# ReflowController_v1_2.net
KiCad netlist of a schematic drawn in EAGLE
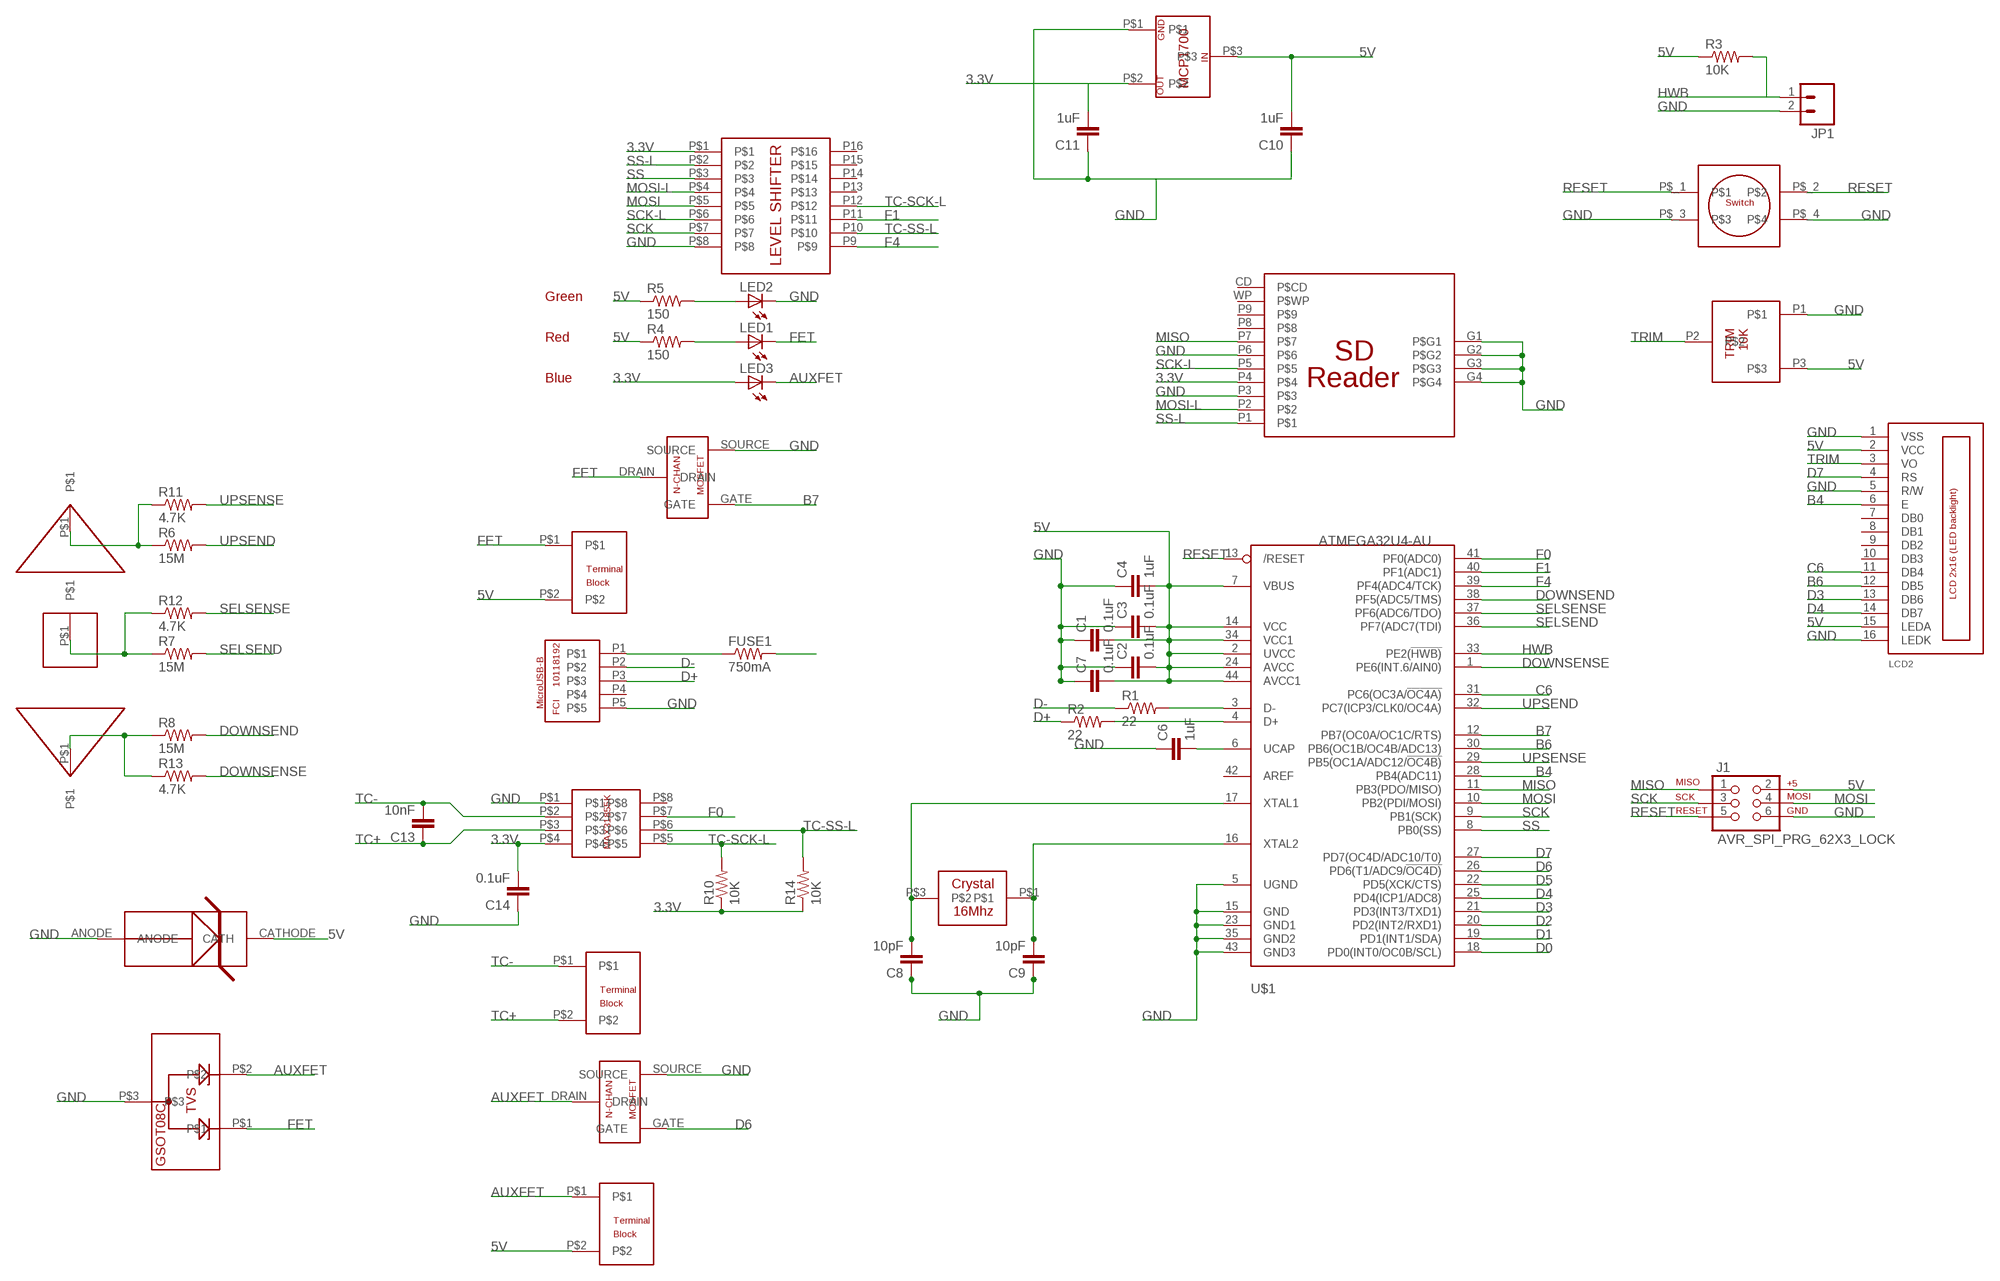
[diagram p0: schematic, sheet 1]

(export (version "E")
  (design (tool "Eeschema 10.0.6"))
  (components
    (comp (ref "C1")
      (value "0.1uF")
      (footprint "eagle-import:0603-CAP")
      (libsource (lib "eagle-import") (part "CAP0603-CAP"))
    )
    (comp (ref "C2")
      (value "0.1uF")
      (footprint "eagle-import:0603-CAP")
      (libsource (lib "eagle-import") (part "CAP0603-CAP"))
    )
    (comp (ref "C3")
      (value "0.1uF")
      (footprint "eagle-import:0603-CAP")
      (libsource (lib "eagle-import") (part "CAP0603-CAP"))
    )
    (comp (ref "C4")
      (value "1uF")
      (footprint "eagle-import:0603-CAP")
      (libsource (lib "eagle-import") (part "CAP0603-CAP"))
    )
    (comp (ref "C6")
      (value "1uF")
      (footprint "eagle-import:0603-CAP")
      (libsource (lib "eagle-import") (part "CAP0603-CAP"))
    )
    (comp (ref "C7")
      (value "0.1uF")
      (footprint "eagle-import:0603-CAP")
      (libsource (lib "eagle-import") (part "CAP0603-CAP"))
    )
    (comp (ref "C8")
      (value "10pF")
      (footprint "eagle-import:0603-CAP")
      (libsource (lib "eagle-import") (part "CAP0603-CAP"))
    )
    (comp (ref "C9")
      (value "10pF")
      (footprint "eagle-import:0603-CAP")
      (libsource (lib "eagle-import") (part "CAP0603-CAP"))
    )
    (comp (ref "C10")
      (value "1uF")
      (footprint "eagle-import:0603-CAP")
      (libsource (lib "eagle-import") (part "CAP0603-CAP"))
    )
    (comp (ref "C11")
      (value "1uF")
      (footprint "eagle-import:0603-CAP")
      (libsource (lib "eagle-import") (part "CAP0603-CAP"))
    )
    (comp (ref "C13")
      (value "10nF")
      (footprint "eagle-import:0603-CAP")
      (libsource (lib "eagle-import") (part "CAP0603-CAP"))
    )
    (comp (ref "C14")
      (value "0.1uF")
      (footprint "eagle-import:0603-CAP")
      (libsource (lib "eagle-import") (part "CAP0603-CAP"))
    )
    (comp (ref "FUSE1")
      (value "750mA")
      (footprint "eagle-import:0603-RES")
      (libsource (lib "eagle-import") (part "RESISTOR0603-RES"))
    )
    (comp (ref "J1")
      (value "AVR_SPI_PRG_62X3_LOCK")
      (footprint "eagle-import:2X3_LOCK")
      (libsource (lib "eagle-import") (part "AVR_SPI_PRG_62X3_LOCK"))
    )
    (comp (ref "JP1")
      (value "M02PTH")
      (footprint "eagle-import:1X02")
      (libsource (lib "eagle-import") (part "M02PTH"))
    )
    (comp (ref "LCD2")
      (value "LCD_2X16_SIL")
      (footprint "eagle-import:HY-1602F")
      (libsource (lib "eagle-import") (part "LCD_2X16_SIL"))
    )
    (comp (ref "LED1")
      (value "LED0603")
      (footprint "eagle-import:LED-0603")
      (libsource (lib "eagle-import") (part "LED0603"))
    )
    (comp (ref "LED2")
      (value "LED0603")
      (footprint "eagle-import:LED-0603")
      (libsource (lib "eagle-import") (part "LED0603"))
    )
    (comp (ref "LED3")
      (value "LED0603")
      (footprint "eagle-import:LED-0603")
      (libsource (lib "eagle-import") (part "LED0603"))
    )
    (comp (ref "R1")
      (value "22")
      (footprint "eagle-import:0603-RES")
      (libsource (lib "eagle-import") (part "RESISTOR0603-RES"))
    )
    (comp (ref "R2")
      (value "22")
      (footprint "eagle-import:0603-RES")
      (libsource (lib "eagle-import") (part "RESISTOR0603-RES"))
    )
    (comp (ref "R3")
      (value "10K")
      (footprint "eagle-import:0603-RES")
      (libsource (lib "eagle-import") (part "RESISTOR0603-RES"))
    )
    (comp (ref "R4")
      (value "150")
      (footprint "eagle-import:0603-RES")
      (libsource (lib "eagle-import") (part "RESISTOR0603-RES"))
    )
    (comp (ref "R5")
      (value "150")
      (footprint "eagle-import:0603-RES")
      (libsource (lib "eagle-import") (part "RESISTOR0603-RES"))
    )
    (comp (ref "R6")
      (value "15M")
      (footprint "eagle-import:0603-RES")
      (libsource (lib "eagle-import") (part "RESISTOR0603-RES"))
    )
    (comp (ref "R7")
      (value "15M")
      (footprint "eagle-import:0603-RES")
      (libsource (lib "eagle-import") (part "RESISTOR0603-RES"))
    )
    (comp (ref "R8")
      (value "15M")
      (footprint "eagle-import:0603-RES")
      (libsource (lib "eagle-import") (part "RESISTOR0603-RES"))
    )
    (comp (ref "R10")
      (value "10K")
      (footprint "eagle-import:0603-RES")
      (libsource (lib "eagle-import") (part "RESISTOR0603-RES"))
    )
    (comp (ref "R11")
      (value "4.7K")
      (footprint "eagle-import:0603-RES")
      (libsource (lib "eagle-import") (part "RESISTOR0603-RES"))
    )
    (comp (ref "R12")
      (value "4.7K")
      (footprint "eagle-import:0603-RES")
      (libsource (lib "eagle-import") (part "RESISTOR0603-RES"))
    )
    (comp (ref "R13")
      (value "4.7K")
      (footprint "eagle-import:0603-RES")
      (libsource (lib "eagle-import") (part "RESISTOR0603-RES"))
    )
    (comp (ref "R14")
      (value "10K")
      (footprint "eagle-import:0603-RES")
      (libsource (lib "eagle-import") (part "RESISTOR0603-RES"))
    )
    (comp (ref "U$1")
      (value "ATMEGA32U4-AU")
      (footprint "eagle-import:TQFP44")
      (libsource (lib "eagle-import") (part "ATMEGA32U4-AU"))
    )
    (comp (ref "U$2")
      (value "16MHZ-CRYSTAL_NX3225GA-16.000M-STD-CRG-1")
      (footprint "eagle-import:16MHZ-CRYSTAL_NX3225GA-16.000M-STD-CRG-1")
      (libsource (lib "eagle-import") (part "16MHZ-CRYSTAL_NX3225GA-16.000M-STD-CRG-1"))
    )
    (comp (ref "U$3")
      (value "USB-B_10118192-0001LF")
      (footprint "eagle-import:USB-B_10118192-0001LF")
      (libsource (lib "eagle-import") (part "USB-B_10118192-0001LF"))
    )
    (comp (ref "U$4")
      (value "SDREADER_2041021-4")
      (footprint "eagle-import:SDREADER_2041021-4")
      (libsource (lib "eagle-import") (part "SDREADER_2041021-4"))
    )
    (comp (ref "U$5")
      (value "2POS_TERM_ED2748-ND")
      (footprint "eagle-import:2POS_TERM_ED2748-ND")
      (libsource (lib "eagle-import") (part "2POS_TERM_ED2748-ND"))
    )
    (comp (ref "U$6")
      (value "N-MOSFET630_DMG1012T-7DICT-ND")
      (footprint "eagle-import:N-MOSFET630_DMG1012T-7DICT-ND")
      (libsource (lib "eagle-import") (part "N-MOSFET630_DMG1012T-7DICT-ND"))
    )
    (comp (ref "U$7")
      (value "2POS_TERM_ED2748-ND")
      (footprint "eagle-import:2POS_TERM_ED2748-ND")
      (libsource (lib "eagle-import") (part "2POS_TERM_ED2748-ND"))
    )
    (comp (ref "U$8")
      (value "NXP_LVL_SHIFT_74HC4050D,653")
      (footprint "eagle-import:NXP_LVL_SHIFT_74HC4050D,653")
      (libsource (lib "eagle-import") (part "NXP_LVL_SHIFT_74HC4050D,653"))
    )
    (comp (ref "U$9")
      (value "MAX_TC_MAX31855KASA+")
      (footprint "eagle-import:MAX_TC_MAX31855KASA+")
      (libsource (lib "eagle-import") (part "MAX_TC_MAX31855KASA+"))
    )
    (comp (ref "U$10")
      (value "10K_TRIM_3362F-1-103LF")
      (footprint "eagle-import:10K_TRIM_3362F-1-103LF")
      (libsource (lib "eagle-import") (part "10K_TRIM_3362F-1-103LF"))
    )
    (comp (ref "U$11")
      (value "MCP1700__LDO")
      (footprint "eagle-import:MCP1700__LDO")
      (libsource (lib "eagle-import") (part "MCP1700__LDO"))
    )
    (comp (ref "U$12")
      (value "MOM-SWITCH-EG4620CT-ND")
      (footprint "eagle-import:MOM-SWITCH-EG4620CT-ND")
      (libsource (lib "eagle-import") (part "MOM-SWITCH-EG4620CT-ND"))
    )
    (comp (ref "U$13")
      (value "CAPTOUCH_ARROW")
      (footprint "eagle-import:CAPTOUCH_ARROW")
      (libsource (lib "eagle-import") (part "CAPTOUCH_ARROW"))
    )
    (comp (ref "U$14")
      (value "CAPTOUCH_ARROW")
      (footprint "eagle-import:CAPTOUCH_ARROW")
      (libsource (lib "eagle-import") (part "CAPTOUCH_ARROW"))
    )
    (comp (ref "U$15")
      (value "CAPTOUCH_SQUARE")
      (footprint "eagle-import:CAPTOUCH_SQUARE")
      (libsource (lib "eagle-import") (part "CAPTOUCH_SQUARE"))
    )
    (comp (ref "U$16")
      (value "N-MOSFET630_DMG1012T-7DICT-ND")
      (footprint "eagle-import:N-MOSFET630_DMG1012T-7DICT-ND")
      (libsource (lib "eagle-import") (part "N-MOSFET630_DMG1012T-7DICT-ND"))
    )
    (comp (ref "U$17")
      (value "2POS_TERM_ED2748-ND")
      (footprint "eagle-import:2POS_TERM_ED2748-ND")
      (libsource (lib "eagle-import") (part "2POS_TERM_ED2748-ND"))
    )
    (comp (ref "U$18")
      (value "TVS_DIODE_MATRIX_GSOT08C-GS08")
      (footprint "eagle-import:TVS_DIODE_MATRIX_GSOT08C-GS08")
      (libsource (lib "eagle-import") (part "TVS_DIODE_MATRIX_GSOT08C-GS08"))
    )
    (comp (ref "U$19")
      (value "TVS_DIODE_1CH_1SMB6.0AT3G")
      (footprint "eagle-import:TVS_DIODE_1CH_1SMB6.0AT3G")
      (libsource (lib "eagle-import") (part "TVS_DIODE_1CH_1SMB6.0AT3G"))
    )
  )
  (nets
    (net (code "1") (name "/3.3V") (class "Default")
      (node (ref "C11") (pin "2") (pinfunction "2_2") (pintype "passive"))
      (node (ref "C14") (pin "2") (pinfunction "2_2") (pintype "passive"))
      (node (ref "LED3") (pin "A") (pinfunction "A_A") (pintype "passive"))
      (node (ref "R10") (pin "1") (pinfunction "1_1") (pintype "passive"))
      (node (ref "R14") (pin "1") (pinfunction "1_1") (pintype "passive"))
      (node (ref "U$11") (pin "P$2") (pinfunction "P$2_P$2") (pintype "bidirectional"))
      (node (ref "U$4") (pin "P4") (pinfunction "P$4_P4") (pintype "bidirectional"))
      (node (ref "U$8") (pin "P$1") (pinfunction "P$1_P$1") (pintype "bidirectional"))
      (node (ref "U$9") (pin "P$4") (pinfunction "P$4_P$4") (pintype "bidirectional"))
    )
    (net (code "2") (name "/5V") (class "Default")
      (node (ref "C1") (pin "2") (pinfunction "2_2") (pintype "passive"))
      (node (ref "C10") (pin "2") (pinfunction "2_2") (pintype "passive"))
      (node (ref "C2") (pin "2") (pinfunction "2_2") (pintype "passive"))
      (node (ref "C3") (pin "2") (pinfunction "2_2") (pintype "passive"))
      (node (ref "C4") (pin "2") (pinfunction "2_2") (pintype "passive"))
      (node (ref "C7") (pin "2") (pinfunction "2_2") (pintype "passive"))
      (node (ref "FUSE1") (pin "2") (pinfunction "2_2") (pintype "passive"))
      (node (ref "J1") (pin "2") (pinfunction "2_2") (pintype "passive"))
      (node (ref "LCD2") (pin "15") (pinfunction "LEDA_15") (pintype "passive"))
      (node (ref "LCD2") (pin "2") (pinfunction "VCC_2") (pintype "power_in"))
      (node (ref "R3") (pin "1") (pinfunction "1_1") (pintype "passive"))
      (node (ref "R4") (pin "1") (pinfunction "1_1") (pintype "passive"))
      (node (ref "R5") (pin "1") (pinfunction "1_1") (pintype "passive"))
      (node (ref "U$1") (pin "14") (pinfunction "VCC_14") (pintype "bidirectional"))
      (node (ref "U$1") (pin "2") (pinfunction "UVCC_2") (pintype "bidirectional"))
      (node (ref "U$1") (pin "24") (pinfunction "AVCC_24") (pintype "bidirectional"))
      (node (ref "U$1") (pin "34") (pinfunction "VCC1_34") (pintype "bidirectional"))
      (node (ref "U$1") (pin "44") (pinfunction "AVCC1_44") (pintype "bidirectional"))
      (node (ref "U$1") (pin "7") (pinfunction "VBUS_7") (pintype "bidirectional"))
      (node (ref "U$10") (pin "P3") (pinfunction "P$3_P3") (pintype "bidirectional"))
      (node (ref "U$11") (pin "P$3") (pinfunction "P$3_P$3") (pintype "bidirectional"))
      (node (ref "U$17") (pin "P$2") (pinfunction "P$2_P$2") (pintype "bidirectional"))
      (node (ref "U$19") (pin "CATHODE") (pinfunction "CATH_CATHODE") (pintype "bidirectional"))
      (node (ref "U$5") (pin "P$2") (pinfunction "P$2_P$2") (pintype "bidirectional"))
    )
    (net (code "3") (name "/AUXFET") (class "Default")
      (node (ref "LED3") (pin "C") (pinfunction "C_C") (pintype "passive"))
      (node (ref "U$16") (pin "DRAIN") (pinfunction "DRAIN_DRAIN") (pintype "bidirectional"))
      (node (ref "U$17") (pin "P$1") (pinfunction "P$1_P$1") (pintype "bidirectional"))
      (node (ref "U$18") (pin "P$2") (pinfunction "P$2_P$2") (pintype "bidirectional"))
    )
    (net (code "4") (name "/B4") (class "Default")
      (node (ref "LCD2") (pin "6") (pinfunction "E_6") (pintype "input"))
      (node (ref "U$1") (pin "28") (pinfunction "PB4(ADC11)_28") (pintype "bidirectional"))
    )
    (net (code "5") (name "/B6") (class "Default")
      (node (ref "LCD2") (pin "12") (pinfunction "DB5_12") (pintype "bidirectional"))
      (node (ref "U$1") (pin "30") (pinfunction "PB6(OC1B/OC4B/ADC13)_30") (pintype "bidirectional"))
    )
    (net (code "6") (name "/B7") (class "Default")
      (node (ref "U$1") (pin "12") (pinfunction "PB7(OC0A/OC1C/RTS)_12") (pintype "bidirectional"))
      (node (ref "U$6") (pin "GATE") (pinfunction "GATE_GATE") (pintype "bidirectional"))
    )
    (net (code "7") (name "/C6") (class "Default")
      (node (ref "LCD2") (pin "11") (pinfunction "DB4_11") (pintype "bidirectional"))
      (node (ref "U$1") (pin "31") (pinfunction "PC6(OC3A/~{OC4A})_31") (pintype "bidirectional"))
    )
    (net (code "8") (name "/D+") (class "Default")
      (node (ref "R2") (pin "1") (pinfunction "1_1") (pintype "passive"))
      (node (ref "U$3") (pin "P3") (pinfunction "P$3_P3") (pintype "bidirectional"))
    )
    (net (code "9") (name "/D-") (class "Default")
      (node (ref "R1") (pin "1") (pinfunction "1_1") (pintype "passive"))
      (node (ref "U$3") (pin "P2") (pinfunction "P$2_P2") (pintype "bidirectional"))
    )
    (net (code "10") (name "/D0") (class "Default")
      (node (ref "U$1") (pin "18") (pinfunction "PD0(INT0/OC0B/SCL)_18") (pintype "bidirectional"))
    )
    (net (code "11") (name "/D1") (class "Default")
      (node (ref "U$1") (pin "19") (pinfunction "PD1(INT1/SDA)_19") (pintype "bidirectional"))
    )
    (net (code "12") (name "/D2") (class "Default")
      (node (ref "U$1") (pin "20") (pinfunction "PD2(INT2/RXD1)_20") (pintype "bidirectional"))
    )
    (net (code "13") (name "/D3") (class "Default")
      (node (ref "LCD2") (pin "13") (pinfunction "DB6_13") (pintype "bidirectional"))
      (node (ref "U$1") (pin "21") (pinfunction "PD3(INT3/TXD1)_21") (pintype "bidirectional"))
    )
    (net (code "14") (name "/D4") (class "Default")
      (node (ref "LCD2") (pin "14") (pinfunction "DB7_14") (pintype "bidirectional"))
      (node (ref "U$1") (pin "25") (pinfunction "PD4(ICP1/ADC8)_25") (pintype "bidirectional"))
    )
    (net (code "15") (name "/D5") (class "Default")
      (node (ref "U$1") (pin "22") (pinfunction "PD5(XCK/CTS)_22") (pintype "bidirectional"))
    )
    (net (code "16") (name "/D6") (class "Default")
      (node (ref "U$1") (pin "26") (pinfunction "PD6(T1/ADC9/~{OC4D})_26") (pintype "bidirectional"))
      (node (ref "U$16") (pin "GATE") (pinfunction "GATE_GATE") (pintype "bidirectional"))
    )
    (net (code "17") (name "/D7") (class "Default")
      (node (ref "LCD2") (pin "4") (pinfunction "RS_4") (pintype "input"))
      (node (ref "U$1") (pin "27") (pinfunction "PD7(OC4D/ADC10/T0)_27") (pintype "bidirectional"))
    )
    (net (code "18") (name "/DOWNSEND") (class "Default")
      (node (ref "R8") (pin "2") (pinfunction "2_2") (pintype "passive"))
      (node (ref "U$1") (pin "38") (pinfunction "PF5(ADC5/TMS)_38") (pintype "bidirectional"))
    )
    (net (code "19") (name "/DOWNSENSE") (class "Default")
      (node (ref "R13") (pin "2") (pinfunction "2_2") (pintype "passive"))
      (node (ref "U$1") (pin "1") (pinfunction "PE6(INT.6/AIN0)_1") (pintype "bidirectional"))
    )
    (net (code "20") (name "/F0") (class "Default")
      (node (ref "U$1") (pin "41") (pinfunction "PF0(ADC0)_41") (pintype "bidirectional"))
      (node (ref "U$9") (pin "P$7") (pinfunction "P$7_P$7") (pintype "bidirectional"))
    )
    (net (code "21") (name "/F1") (class "Default")
      (node (ref "U$1") (pin "40") (pinfunction "PF1(ADC1)_40") (pintype "bidirectional"))
      (node (ref "U$8") (pin "P11") (pinfunction "P$11_P11") (pintype "bidirectional"))
    )
    (net (code "22") (name "/F4") (class "Default")
      (node (ref "U$1") (pin "39") (pinfunction "PF4(ADC4/TCK)_39") (pintype "bidirectional"))
      (node (ref "U$8") (pin "P9") (pinfunction "P$9_P9") (pintype "bidirectional"))
    )
    (net (code "23") (name "/FET") (class "Default")
      (node (ref "LED1") (pin "C") (pinfunction "C_C") (pintype "passive"))
      (node (ref "U$18") (pin "P$1") (pinfunction "P$1_P$1") (pintype "bidirectional"))
      (node (ref "U$5") (pin "P$1") (pinfunction "P$1_P$1") (pintype "bidirectional"))
      (node (ref "U$6") (pin "DRAIN") (pinfunction "DRAIN_DRAIN") (pintype "bidirectional"))
    )
    (net (code "24") (name "/GND") (class "Default")
      (node (ref "C1") (pin "1") (pinfunction "1_1") (pintype "passive"))
      (node (ref "C10") (pin "1") (pinfunction "1_1") (pintype "passive"))
      (node (ref "C11") (pin "1") (pinfunction "1_1") (pintype "passive"))
      (node (ref "C14") (pin "1") (pinfunction "1_1") (pintype "passive"))
      (node (ref "C2") (pin "1") (pinfunction "1_1") (pintype "passive"))
      (node (ref "C3") (pin "1") (pinfunction "1_1") (pintype "passive"))
      (node (ref "C4") (pin "1") (pinfunction "1_1") (pintype "passive"))
      (node (ref "C6") (pin "1") (pinfunction "1_1") (pintype "passive"))
      (node (ref "C7") (pin "1") (pinfunction "1_1") (pintype "passive"))
      (node (ref "C8") (pin "1") (pinfunction "1_1") (pintype "passive"))
      (node (ref "C9") (pin "1") (pinfunction "1_1") (pintype "passive"))
      (node (ref "J1") (pin "6") (pinfunction "6_6") (pintype "passive"))
      (node (ref "JP1") (pin "2") (pinfunction "2_2") (pintype "passive"))
      (node (ref "LCD2") (pin "1") (pinfunction "VSS_1") (pintype "power_in"))
      (node (ref "LCD2") (pin "16") (pinfunction "LEDK_16") (pintype "passive"))
      (node (ref "LCD2") (pin "5") (pinfunction "R/W_5") (pintype "input"))
      (node (ref "LED2") (pin "C") (pinfunction "C_C") (pintype "passive"))
      (node (ref "U$1") (pin "15") (pinfunction "GND_15") (pintype "bidirectional"))
      (node (ref "U$1") (pin "23") (pinfunction "GND1_23") (pintype "bidirectional"))
      (node (ref "U$1") (pin "35") (pinfunction "GND2_35") (pintype "bidirectional"))
      (node (ref "U$1") (pin "43") (pinfunction "GND3_43") (pintype "bidirectional"))
      (node (ref "U$1") (pin "5") (pinfunction "UGND_5") (pintype "bidirectional"))
      (node (ref "U$10") (pin "P1") (pinfunction "P$1_P1") (pintype "bidirectional"))
      (node (ref "U$11") (pin "P$1") (pinfunction "P$1_P$1") (pintype "bidirectional"))
      (node (ref "U$12") (pin "P$_3") (pinfunction "P$3_P$_3") (pintype "bidirectional"))
      (node (ref "U$12") (pin "P$_4") (pinfunction "P$4_P$_4") (pintype "bidirectional"))
      (node (ref "U$16") (pin "SOURCE") (pinfunction "SOURCE_SOURCE") (pintype "bidirectional"))
      (node (ref "U$18") (pin "P$3") (pinfunction "P$3_P$3") (pintype "bidirectional"))
      (node (ref "U$19") (pin "ANODE") (pinfunction "ANODE_ANODE") (pintype "bidirectional"))
      (node (ref "U$3") (pin "P5") (pinfunction "P$5_P5") (pintype "bidirectional"))
      (node (ref "U$4") (pin "G1") (pinfunction "P$G1_G1") (pintype "bidirectional"))
      (node (ref "U$4") (pin "G2") (pinfunction "P$G2_G2") (pintype "bidirectional"))
      (node (ref "U$4") (pin "G3") (pinfunction "P$G3_G3") (pintype "bidirectional"))
      (node (ref "U$4") (pin "G4") (pinfunction "P$G4_G4") (pintype "bidirectional"))
      (node (ref "U$4") (pin "P3") (pinfunction "P$3_P3") (pintype "bidirectional"))
      (node (ref "U$4") (pin "P6") (pinfunction "P$6_P6") (pintype "bidirectional"))
      (node (ref "U$6") (pin "SOURCE") (pinfunction "SOURCE_SOURCE") (pintype "bidirectional"))
      (node (ref "U$8") (pin "P$8") (pinfunction "P$8_P$8") (pintype "bidirectional"))
      (node (ref "U$9") (pin "P$1") (pinfunction "P$1_P$1") (pintype "bidirectional"))
    )
    (net (code "25") (name "/HWB") (class "Default")
      (node (ref "JP1") (pin "1") (pinfunction "1_1") (pintype "passive"))
      (node (ref "R3") (pin "2") (pinfunction "2_2") (pintype "passive"))
      (node (ref "U$1") (pin "33") (pinfunction "PE2(~{HWB})_33") (pintype "bidirectional"))
    )
    (net (code "26") (name "/MISO") (class "Default")
      (node (ref "J1") (pin "1") (pinfunction "1_1") (pintype "passive"))
      (node (ref "U$1") (pin "11") (pinfunction "PB3(PDO/MISO)_11") (pintype "bidirectional"))
      (node (ref "U$4") (pin "P7") (pinfunction "P$7_P7") (pintype "bidirectional"))
    )
    (net (code "27") (name "/MOSI") (class "Default")
      (node (ref "J1") (pin "4") (pinfunction "4_4") (pintype "passive"))
      (node (ref "U$1") (pin "10") (pinfunction "PB2(PDI/MOSI)_10") (pintype "bidirectional"))
      (node (ref "U$8") (pin "P$5") (pinfunction "P$5_P$5") (pintype "bidirectional"))
    )
    (net (code "28") (name "/MOSI-L") (class "Default")
      (node (ref "U$4") (pin "P2") (pinfunction "P$2_P2") (pintype "bidirectional"))
      (node (ref "U$8") (pin "P$4") (pinfunction "P$4_P$4") (pintype "bidirectional"))
    )
    (net (code "29") (name "/RESET") (class "Default")
      (node (ref "J1") (pin "5") (pinfunction "5_5") (pintype "passive"))
      (node (ref "U$1") (pin "13") (pinfunction "/RESET_13") (pintype "bidirectional"))
      (node (ref "U$12") (pin "P$_1") (pinfunction "P$1_P$_1") (pintype "bidirectional"))
      (node (ref "U$12") (pin "P$_2") (pinfunction "P$2_P$_2") (pintype "bidirectional"))
    )
    (net (code "30") (name "/SCK") (class "Default")
      (node (ref "J1") (pin "3") (pinfunction "3_3") (pintype "passive"))
      (node (ref "U$1") (pin "9") (pinfunction "PB1(SCK)_9") (pintype "bidirectional"))
      (node (ref "U$8") (pin "P$7") (pinfunction "P$7_P$7") (pintype "bidirectional"))
    )
    (net (code "31") (name "/SCK-L") (class "Default")
      (node (ref "U$4") (pin "P5") (pinfunction "P$5_P5") (pintype "bidirectional"))
      (node (ref "U$8") (pin "P$6") (pinfunction "P$6_P$6") (pintype "bidirectional"))
    )
    (net (code "32") (name "/SELSEND") (class "Default")
      (node (ref "R7") (pin "2") (pinfunction "2_2") (pintype "passive"))
      (node (ref "U$1") (pin "36") (pinfunction "PF7(ADC7(TDI)_36") (pintype "bidirectional"))
    )
    (net (code "33") (name "/SELSENSE") (class "Default")
      (node (ref "R12") (pin "2") (pinfunction "2_2") (pintype "passive"))
      (node (ref "U$1") (pin "37") (pinfunction "PF6(ADC6/TDO)_37") (pintype "bidirectional"))
    )
    (net (code "34") (name "/SS") (class "Default")
      (node (ref "U$1") (pin "8") (pinfunction "PB0(SS)_8") (pintype "bidirectional"))
      (node (ref "U$8") (pin "P$3") (pinfunction "P$3_P$3") (pintype "bidirectional"))
    )
    (net (code "35") (name "/SS-L") (class "Default")
      (node (ref "U$4") (pin "P1") (pinfunction "P$1_P1") (pintype "bidirectional"))
      (node (ref "U$8") (pin "P$2") (pinfunction "P$2_P$2") (pintype "bidirectional"))
    )
    (net (code "36") (name "/TC+") (class "Default")
      (node (ref "C13") (pin "1") (pinfunction "1_1") (pintype "passive"))
      (node (ref "U$7") (pin "P$2") (pinfunction "P$2_P$2") (pintype "bidirectional"))
      (node (ref "U$9") (pin "P$3") (pinfunction "P$3_P$3") (pintype "bidirectional"))
    )
    (net (code "37") (name "/TC-") (class "Default")
      (node (ref "C13") (pin "2") (pinfunction "2_2") (pintype "passive"))
      (node (ref "U$7") (pin "P$1") (pinfunction "P$1_P$1") (pintype "bidirectional"))
      (node (ref "U$9") (pin "P$2") (pinfunction "P$2_P$2") (pintype "bidirectional"))
    )
    (net (code "38") (name "/TC-SCK-L") (class "Default")
      (node (ref "R10") (pin "2") (pinfunction "2_2") (pintype "passive"))
      (node (ref "U$8") (pin "P12") (pinfunction "P$12_P12") (pintype "bidirectional"))
      (node (ref "U$9") (pin "P$5") (pinfunction "P$5_P$5") (pintype "bidirectional"))
    )
    (net (code "39") (name "/TC-SS-L") (class "Default")
      (node (ref "R14") (pin "2") (pinfunction "2_2") (pintype "passive"))
      (node (ref "U$8") (pin "P10") (pinfunction "P$10_P10") (pintype "bidirectional"))
      (node (ref "U$9") (pin "P$6") (pinfunction "P$6_P$6") (pintype "bidirectional"))
    )
    (net (code "40") (name "/TRIM") (class "Default")
      (node (ref "LCD2") (pin "3") (pinfunction "VO_3") (pintype "input"))
      (node (ref "U$10") (pin "P2") (pinfunction "P$2_P2") (pintype "bidirectional"))
    )
    (net (code "41") (name "/UPSEND") (class "Default")
      (node (ref "R6") (pin "2") (pinfunction "2_2") (pintype "passive"))
      (node (ref "U$1") (pin "32") (pinfunction "PC7(ICP3/CLK0/OC4A)_32") (pintype "bidirectional"))
    )
    (net (code "42") (name "/UPSENSE") (class "Default")
      (node (ref "R11") (pin "2") (pinfunction "2_2") (pintype "passive"))
      (node (ref "U$1") (pin "29") (pinfunction "PB5(OC1A/ADC12/~{OC4B})_29") (pintype "bidirectional"))
    )
    (net (code "43") (name "Net-(LED1-PadA)") (class "Default")
      (node (ref "LED1") (pin "A") (pinfunction "A_A") (pintype "passive"))
      (node (ref "R4") (pin "2") (pinfunction "2_2") (pintype "passive"))
    )
    (net (code "44") (name "Net-(LED2-PadA)") (class "Default")
      (node (ref "LED2") (pin "A") (pinfunction "A_A") (pintype "passive"))
      (node (ref "R5") (pin "2") (pinfunction "2_2") (pintype "passive"))
    )
    (net (code "45") (name "Net-(R11-Pad1)") (class "Default")
      (node (ref "R11") (pin "1") (pinfunction "1_1") (pintype "passive"))
      (node (ref "R6") (pin "1") (pinfunction "1_1") (pintype "passive"))
      (node (ref "U$13") (pin "P$1") (pinfunction "P$1_P$1") (pintype "bidirectional"))
    )
    (net (code "46") (name "Net-(R12-Pad1)") (class "Default")
      (node (ref "R12") (pin "1") (pinfunction "1_1") (pintype "passive"))
      (node (ref "R7") (pin "1") (pinfunction "1_1") (pintype "passive"))
      (node (ref "U$15") (pin "P$1") (pinfunction "P$1_P$1") (pintype "bidirectional"))
    )
    (net (code "47") (name "Net-(R13-Pad1)") (class "Default")
      (node (ref "R13") (pin "1") (pinfunction "1_1") (pintype "passive"))
      (node (ref "R8") (pin "1") (pinfunction "1_1") (pintype "passive"))
      (node (ref "U$14") (pin "P$1") (pinfunction "P$1_P$1") (pintype "bidirectional"))
    )
    (net (code "48") (name "Net-(U$1-D+)") (class "Default")
      (node (ref "R2") (pin "2") (pinfunction "2_2") (pintype "passive"))
      (node (ref "U$1") (pin "4") (pinfunction "D+_4") (pintype "bidirectional"))
    )
    (net (code "49") (name "Net-(U$1-D-)") (class "Default")
      (node (ref "R1") (pin "2") (pinfunction "2_2") (pintype "passive"))
      (node (ref "U$1") (pin "3") (pinfunction "D-_3") (pintype "bidirectional"))
    )
    (net (code "50") (name "Net-(U$1-UCAP)") (class "Default")
      (node (ref "C6") (pin "2") (pinfunction "2_2") (pintype "passive"))
      (node (ref "U$1") (pin "6") (pinfunction "UCAP_6") (pintype "bidirectional"))
    )
    (net (code "51") (name "Net-(U$1-XTAL1)") (class "Default")
      (node (ref "C8") (pin "2") (pinfunction "2_2") (pintype "passive"))
      (node (ref "U$1") (pin "17") (pinfunction "XTAL1_17") (pintype "bidirectional"))
      (node (ref "U$2") (pin "P$3") (pinfunction "P$2_P$3") (pintype "bidirectional"))
    )
    (net (code "52") (name "Net-(U$1-XTAL2)") (class "Default")
      (node (ref "C9") (pin "2") (pinfunction "2_2") (pintype "passive"))
      (node (ref "U$1") (pin "16") (pinfunction "XTAL2_16") (pintype "bidirectional"))
      (node (ref "U$2") (pin "P$1") (pinfunction "P$1_P$1") (pintype "bidirectional"))
    )
    (net (code "53") (name "Net-(U$3-P$1)") (class "Default")
      (node (ref "FUSE1") (pin "1") (pinfunction "1_1") (pintype "passive"))
      (node (ref "U$3") (pin "P1") (pinfunction "P$1_P1") (pintype "bidirectional"))
    )
    (net (code "54") (name "unconnected-(LCD2-DB0-Pad7)") (class "Default")
      (node (ref "LCD2") (pin "7") (pinfunction "DB0_7") (pintype "bidirectional"))
    )
    (net (code "55") (name "unconnected-(LCD2-DB1-Pad8)") (class "Default")
      (node (ref "LCD2") (pin "8") (pinfunction "DB1_8") (pintype "bidirectional"))
    )
    (net (code "56") (name "unconnected-(LCD2-DB2-Pad9)") (class "Default")
      (node (ref "LCD2") (pin "9") (pinfunction "DB2_9") (pintype "bidirectional"))
    )
    (net (code "57") (name "unconnected-(LCD2-DB3-Pad10)") (class "Default")
      (node (ref "LCD2") (pin "10") (pinfunction "DB3_10") (pintype "bidirectional"))
    )
    (net (code "58") (name "unconnected-(U$1-AREF-Pad42)") (class "Default")
      (node (ref "U$1") (pin "42") (pinfunction "AREF_42") (pintype "bidirectional"))
    )
    (net (code "59") (name "unconnected-(U$3-P$4-PadP4)") (class "Default")
      (node (ref "U$3") (pin "P4") (pinfunction "P$4_P4") (pintype "bidirectional"))
    )
    (net (code "60") (name "unconnected-(U$4-P$8-PadP8)") (class "Default")
      (node (ref "U$4") (pin "P8") (pinfunction "P$8_P8") (pintype "bidirectional"))
    )
    (net (code "61") (name "unconnected-(U$4-P$9-PadP9)") (class "Default")
      (node (ref "U$4") (pin "P9") (pinfunction "P$9_P9") (pintype "bidirectional"))
    )
    (net (code "62") (name "unconnected-(U$4-P$CD-PadCD)") (class "Default")
      (node (ref "U$4") (pin "CD") (pinfunction "P$CD_CD") (pintype "bidirectional"))
    )
    (net (code "63") (name "unconnected-(U$4-P$WP-PadWP)") (class "Default")
      (node (ref "U$4") (pin "WP") (pinfunction "P$WP_WP") (pintype "bidirectional"))
    )
    (net (code "64") (name "unconnected-(U$8-P$13-PadP13)") (class "Default")
      (node (ref "U$8") (pin "P13") (pinfunction "P$13_P13") (pintype "bidirectional"))
    )
    (net (code "65") (name "unconnected-(U$8-P$14-PadP14)") (class "Default")
      (node (ref "U$8") (pin "P14") (pinfunction "P$14_P14") (pintype "bidirectional"))
    )
    (net (code "66") (name "unconnected-(U$8-P$15-PadP15)") (class "Default")
      (node (ref "U$8") (pin "P15") (pinfunction "P$15_P15") (pintype "bidirectional"))
    )
    (net (code "67") (name "unconnected-(U$8-P$16-PadP16)") (class "Default")
      (node (ref "U$8") (pin "P16") (pinfunction "P$16_P16") (pintype "bidirectional"))
    )
    (net (code "68") (name "unconnected-(U$9-PadP$8)") (class "Default")
      (node (ref "U$9") (pin "P$8") (pinfunction "P$8_P$8") (pintype "bidirectional"))
    )
  )
)
